# MS5803-02BAv2.net
KiCad netlist of a schematic drawn in EAGLE
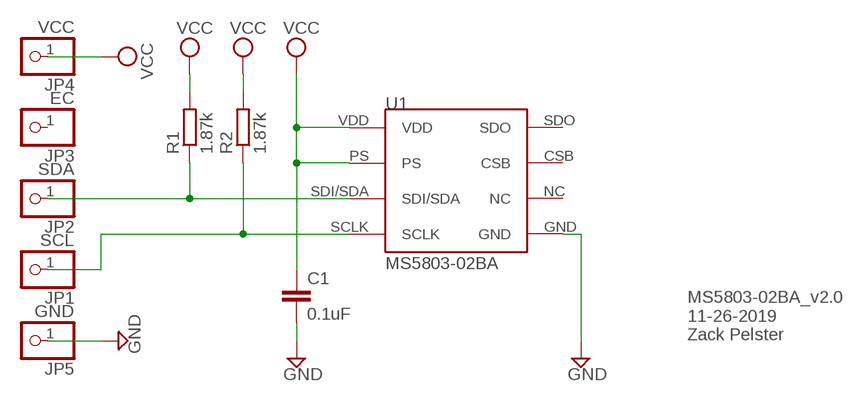
[diagram p0: schematic, sheet 1]

(export (version "E")
  (design (tool "Eeschema 10.0.6"))
  (components
    (comp (ref "C1")
      (value "0.1uF")
      (footprint "eagle-import:C0805")
      (libsource (lib "eagle-import") (part "C-EUC0805"))
    )
    (comp (ref "JP1")
      (value "SCL")
      (footprint "eagle-import:1X01")
      (libsource (lib "eagle-import") (part "PINHD-1X1"))
    )
    (comp (ref "JP2")
      (value "SDA")
      (footprint "eagle-import:1X01")
      (libsource (lib "eagle-import") (part "PINHD-1X1"))
    )
    (comp (ref "JP3")
      (value "EC")
      (footprint "eagle-import:1X01")
      (libsource (lib "eagle-import") (part "PINHD-1X1"))
    )
    (comp (ref "JP4")
      (value "VCC")
      (footprint "eagle-import:1X01")
      (libsource (lib "eagle-import") (part "PINHD-1X1"))
    )
    (comp (ref "JP5")
      (value "GND")
      (footprint "eagle-import:1X01")
      (libsource (lib "eagle-import") (part "PINHD-1X1"))
    )
    (comp (ref "R1")
      (value "1.87k")
      (footprint "eagle-import:R0805")
      (libsource (lib "eagle-import") (part "R-EU_R0805"))
    )
    (comp (ref "R2")
      (value "1.87k")
      (footprint "eagle-import:R0805")
      (libsource (lib "eagle-import") (part "R-EU_R0805"))
    )
    (comp (ref "U1")
      (value "MS5803-02BA")
      (footprint "eagle-import:MS5803-02BA")
      (libsource (lib "eagle-import") (part "MS5803-02BA"))
    )
  )
  (nets
    (net (code "1") (name "GND") (class "Default")
      (node (ref "C1") (pin "2") (pinfunction "2_2") (pintype "passive"))
      (node (ref "JP5") (pin "1") (pinfunction "1_1") (pintype "passive"))
      (node (ref "U1") (pin "GND") (pinfunction "GND_GND") (pintype "bidirectional"))
    )
    (net (code "2") (name "Net-(JP1-Pad1)") (class "Default")
      (node (ref "JP1") (pin "1") (pinfunction "1_1") (pintype "passive"))
      (node (ref "R2") (pin "1") (pinfunction "1_1") (pintype "passive"))
      (node (ref "U1") (pin "SCLK") (pinfunction "SCLK_SCLK") (pintype "bidirectional"))
    )
    (net (code "3") (name "Net-(JP2-Pad1)") (class "Default")
      (node (ref "JP2") (pin "1") (pinfunction "1_1") (pintype "passive"))
      (node (ref "R1") (pin "1") (pinfunction "1_1") (pintype "passive"))
      (node (ref "U1") (pin "SDI/SDA") (pinfunction "SDI/SDA_SDI/SDA") (pintype "bidirectional"))
    )
    (net (code "4") (name "VCC") (class "Default")
      (node (ref "C1") (pin "1") (pinfunction "1_1") (pintype "passive"))
      (node (ref "JP4") (pin "1") (pinfunction "1_1") (pintype "passive"))
      (node (ref "R1") (pin "2") (pinfunction "2_2") (pintype "passive"))
      (node (ref "R2") (pin "2") (pinfunction "2_2") (pintype "passive"))
      (node (ref "U1") (pin "PS") (pinfunction "PS_PS") (pintype "bidirectional"))
      (node (ref "U1") (pin "VDD") (pinfunction "VDD_VDD") (pintype "bidirectional"))
    )
    (net (code "5") (name "unconnected-(JP3-Pad1)") (class "Default")
      (node (ref "JP3") (pin "1") (pinfunction "1_1") (pintype "passive"))
    )
    (net (code "6") (name "unconnected-(U1-PadCSB)") (class "Default")
      (node (ref "U1") (pin "CSB") (pinfunction "CSB_CSB") (pintype "bidirectional"))
    )
    (net (code "7") (name "unconnected-(U1-PadNC)") (class "Default")
      (node (ref "U1") (pin "NC") (pinfunction "NC_NC") (pintype "bidirectional"))
    )
    (net (code "8") (name "unconnected-(U1-PadSDO)") (class "Default")
      (node (ref "U1") (pin "SDO") (pinfunction "SDO_SDO") (pintype "bidirectional"))
    )
  )
)
